# armTempSch.net
KiCad netlist of a schematic drawn in EAGLE
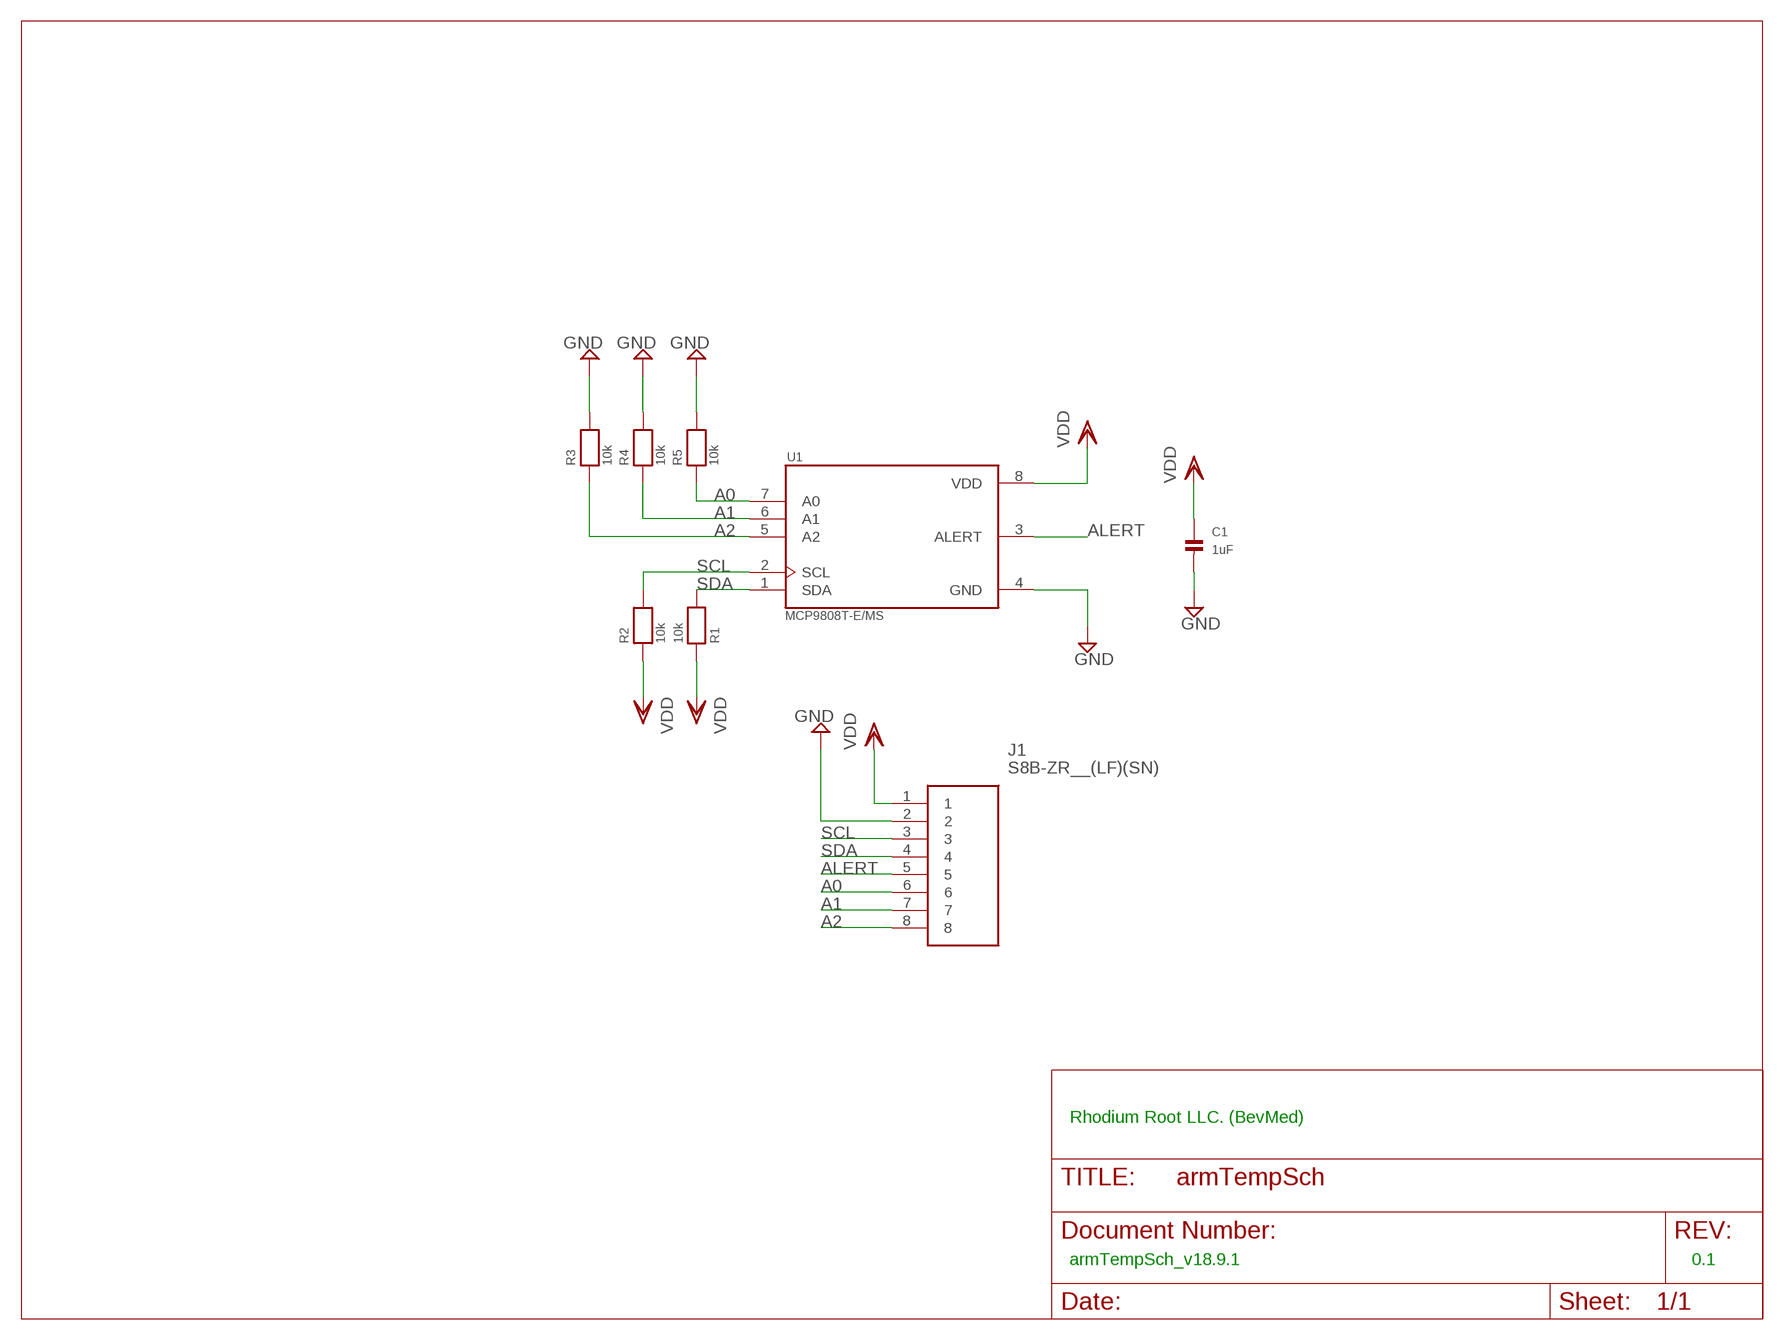
[diagram p0: schematic, sheet 1]

(export (version "E")
  (design (tool "Eeschema 10.0.6"))
  (components
    (comp (ref "C1")
      (value "1uF")
      (footprint "eagle-import:_0805")
      (fields (field (name "MPN") "MCTT21X105K160CT"))
      (libsource (lib "eagle-import") (part "CAP_CERAMIC_0805"))
    )
    (comp (ref "J1")
      (value "S8B-ZR__(LF)(SN)")
      (footprint "eagle-import:SHDR8W50P0X150_1X8_1350X600X37")
      (fields
        (field (name "ARROW_PART_NUMBER") "S8B-ZR  (LF)(SN)")
        (field (name "RS_PART_NUMBER") "1724983")
        (field (name "MPN") "S8B-ZR")
      )
      (libsource (lib "eagle-import") (part "S8B-ZR__(LF)(SN)"))
    )
    (comp (ref "R1")
      (value "10k")
      (footprint "eagle-import:0805")
      (fields (field (name "MPN") "ERJ-6GEYJ103V"))
      (libsource (lib "eagle-import") (part "RESISTOR0805"))
    )
    (comp (ref "R2")
      (value "10k")
      (footprint "eagle-import:0805")
      (fields (field (name "MPN") "ERJ-6GEYJ103V"))
      (libsource (lib "eagle-import") (part "RESISTOR0805"))
    )
    (comp (ref "R3")
      (value "10k")
      (footprint "eagle-import:0805")
      (fields (field (name "MPN") "ERJ-6GEYJ103V"))
      (libsource (lib "eagle-import") (part "RESISTOR0805"))
    )
    (comp (ref "R4")
      (value "10k")
      (footprint "eagle-import:0805")
      (fields (field (name "MPN") "ERJ-6GEYJ103V"))
      (libsource (lib "eagle-import") (part "RESISTOR0805"))
    )
    (comp (ref "R5")
      (value "10k")
      (footprint "eagle-import:0805")
      (fields (field (name "MPN") "ERJ-6GEYJ103V"))
      (libsource (lib "eagle-import") (part "RESISTOR0805"))
    )
    (comp (ref "U1")
      (value "MCP9808T-E/MS")
      (footprint "eagle-import:SOP65P490X110-8N")
      (fields (field (name "MF") "Microchip"))
      (libsource (lib "eagle-import") (part "MCP9808T-E/MS"))
    )
  )
  (nets
    (net (code "1") (name "/A0") (class "Default")
      (node (ref "J1") (pin "6") (pinfunction "6_6") (pintype "bidirectional"))
      (node (ref "R5") (pin "1") (pinfunction "1_1") (pintype "passive"))
      (node (ref "U1") (pin "7") (pinfunction "A0_7") (pintype "input"))
    )
    (net (code "2") (name "/A1") (class "Default")
      (node (ref "J1") (pin "7") (pinfunction "7_7") (pintype "bidirectional"))
      (node (ref "R4") (pin "1") (pinfunction "1_1") (pintype "passive"))
      (node (ref "U1") (pin "6") (pinfunction "A1_6") (pintype "input"))
    )
    (net (code "3") (name "/A2") (class "Default")
      (node (ref "J1") (pin "8") (pinfunction "8_8") (pintype "bidirectional"))
      (node (ref "R3") (pin "1") (pinfunction "1_1") (pintype "passive"))
      (node (ref "U1") (pin "5") (pinfunction "A2_5") (pintype "input"))
    )
    (net (code "4") (name "/ALERT") (class "Default")
      (node (ref "J1") (pin "5") (pinfunction "5_5") (pintype "bidirectional"))
      (node (ref "U1") (pin "3") (pinfunction "ALERT_3") (pintype "output"))
    )
    (net (code "5") (name "/SCL") (class "Default")
      (node (ref "J1") (pin "3") (pinfunction "3_3") (pintype "bidirectional"))
      (node (ref "R2") (pin "2") (pinfunction "2_2") (pintype "passive"))
      (node (ref "U1") (pin "2") (pinfunction "SCL_2") (pintype "input"))
    )
    (net (code "6") (name "/SDA") (class "Default")
      (node (ref "J1") (pin "4") (pinfunction "4_4") (pintype "bidirectional"))
      (node (ref "R1") (pin "2") (pinfunction "2_2") (pintype "passive"))
      (node (ref "U1") (pin "1") (pinfunction "SDA_1") (pintype "bidirectional"))
    )
    (net (code "7") (name "GND") (class "Default")
      (node (ref "C1") (pin "2") (pinfunction "P$2_2") (pintype "passive"))
      (node (ref "J1") (pin "2") (pinfunction "2_2") (pintype "bidirectional"))
      (node (ref "R3") (pin "2") (pinfunction "2_2") (pintype "passive"))
      (node (ref "R4") (pin "2") (pinfunction "2_2") (pintype "passive"))
      (node (ref "R5") (pin "2") (pinfunction "2_2") (pintype "passive"))
      (node (ref "U1") (pin "4") (pinfunction "GND_4") (pintype "power_in"))
    )
    (net (code "8") (name "VDD") (class "Default")
      (node (ref "C1") (pin "1") (pinfunction "P$1_1") (pintype "passive"))
      (node (ref "J1") (pin "1") (pinfunction "1_1") (pintype "bidirectional"))
      (node (ref "R1") (pin "1") (pinfunction "1_1") (pintype "passive"))
      (node (ref "R2") (pin "1") (pinfunction "1_1") (pintype "passive"))
      (node (ref "U1") (pin "8") (pinfunction "VDD_8") (pintype "power_in"))
    )
  )
)
